# Wifi.net
KiCad netlist of a schematic drawn in Altium Designer
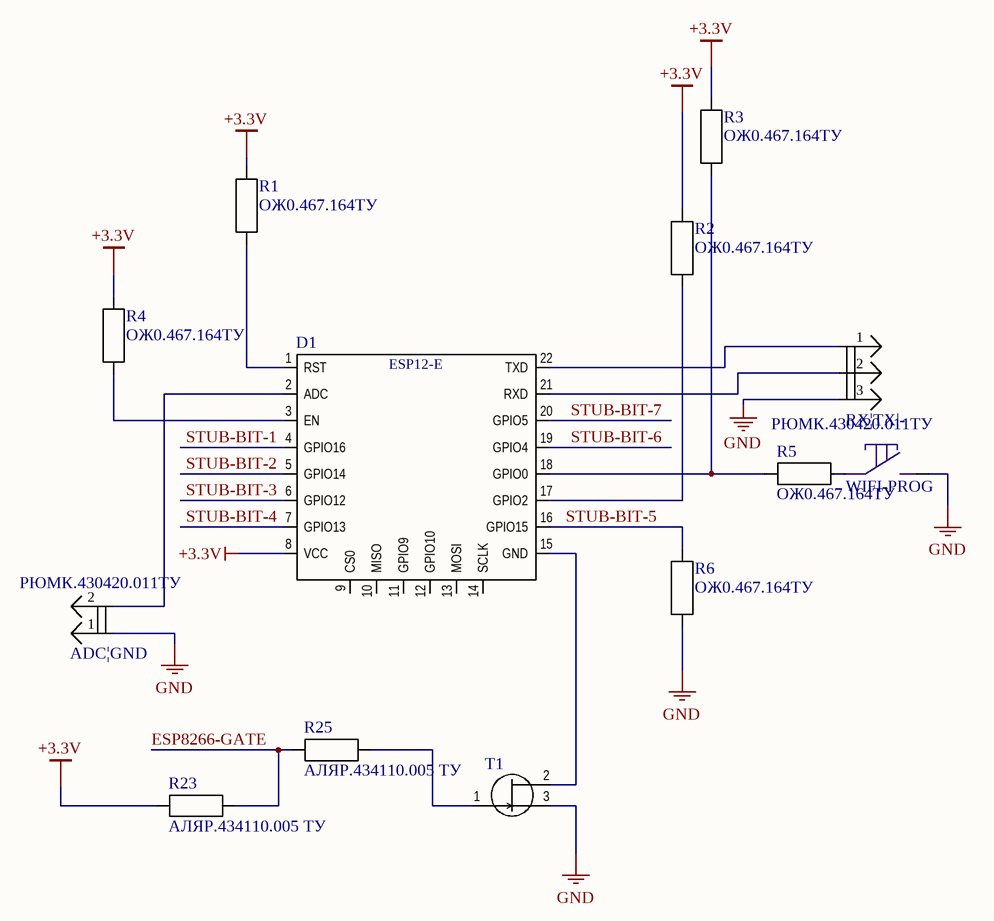
[diagram p0: Wifi модуль.SchDoc]

(export (version "E")
  (design (tool "Eeschema 10.0.6"))
  (components
    (comp (ref "ADC¦GND")
      (value "РЮМК.430420.011ТУ")
      (footprint "СНП346-2ВП21-1")
      (fields (field (name "MANUFACTURERPARTNUMBER") "Вилка СНП346-2ВП21-1"))
      (libsource (lib "РАЗЪЕМЫ") (part "СНП346-2ВП21-1"))
    )
    (comp (ref "D1")
      (value "~")
      (footprint "ESP12-E")
      (fields (field (name "MANUFACTURER") "ESPRESSIF") (field (name "MANUFACTURERPARTNUMBER") "ESP12E"))
      (libsource (lib "МИКРОСХЕМЫ") (part "ESP12-E"))
    )
    (comp (ref "R1")
      (value "ОЖ0.467.164ТУ")
      (footprint "Р1-8МП-0,125")
      (fields
        (field (name "TOLERANCE") "±1%-0,5-Л")
        (field (name "MANUFACTURERPARTNUMBER") "Р1-8МП-0,125-100 Ом±1%-0,5-Л")
      )
      (libsource (lib "РЕЗИСТОРЫ") (part "Р1-8МП-0,125-100 Ом±1%"))
    )
    (comp (ref "R2")
      (value "ОЖ0.467.164ТУ")
      (footprint "Р1-8МП-0,125")
      (fields
        (field (name "TOLERANCE") "±1%-0,5-Л")
        (field (name "MANUFACTURERPARTNUMBER") "Р1-8МП-0,125-100 Ом±1%-0,5-Л")
      )
      (libsource (lib "РЕЗИСТОРЫ") (part "Р1-8МП-0,125-100 Ом±1%"))
    )
    (comp (ref "R3")
      (value "ОЖ0.467.164ТУ")
      (footprint "Р1-8МП-0,125")
      (fields
        (field (name "TOLERANCE") "±1%-0,5-Л")
        (field (name "MANUFACTURERPARTNUMBER") "Р1-8МП-0,125-100 Ом±1%-0,5-Л")
      )
      (libsource (lib "РЕЗИСТОРЫ") (part "Р1-8МП-0,125-100 Ом±1%"))
    )
    (comp (ref "R4")
      (value "ОЖ0.467.164ТУ")
      (footprint "Р1-8МП-0,125")
      (fields
        (field (name "TOLERANCE") "±1%-0,5-Л")
        (field (name "MANUFACTURERPARTNUMBER") "Р1-8МП-0,125-100 Ом±1%-0,5-Л")
      )
      (libsource (lib "РЕЗИСТОРЫ") (part "Р1-8МП-0,125-100 Ом±1%"))
    )
    (comp (ref "R5")
      (value "ОЖ0.467.164ТУ")
      (footprint "Р1-8МП-0,125")
      (fields
        (field (name "TOLERANCE") "±1%-0,5-Л")
        (field (name "MANUFACTURERPARTNUMBER") "Р1-8МП-0,125-100 Ом±1%-0,5-Л")
      )
      (libsource (lib "РЕЗИСТОРЫ") (part "Р1-8МП-0,125-100 Ом±1%"))
    )
    (comp (ref "R6")
      (value "ОЖ0.467.164ТУ")
      (footprint "Р1-8МП-0,125")
      (fields
        (field (name "TOLERANCE") "±1%-0,5-Л")
        (field (name "MANUFACTURERPARTNUMBER") "Р1-8МП-0,125-100 Ом±1%-0,5-Л")
      )
      (libsource (lib "РЕЗИСТОРЫ") (part "Р1-8МП-0,125-100 Ом±1%"))
    )
    (comp (ref "R23")
      (value "АЛЯР.434110.005 ТУ")
      (footprint "Р1-12-0,125")
      (fields
        (field (name "TOLERANCE") "±1%-Л")
        (field (name "MANUFACTURERPARTNUMBER") "Р1-12-0,125-1,5 кОм±1%-Л")
      )
      (libsource (lib "РЕЗИСТОРЫ") (part "Р1-12-0,125-1,5 кОм±1%"))
    )
    (comp (ref "R25")
      (value "АЛЯР.434110.005 ТУ")
      (footprint "Р1-12-0,125")
      (fields
        (field (name "TOLERANCE") "±5%-Л")
        (field (name "MANUFACTURERPARTNUMBER") "Р1-12-0,125-200 Ом±5%-Л")
      )
      (libsource (lib "РЕЗИСТОРЫ") (part "Р1-12-0,125-200 Ом±5%"))
    )
    (comp (ref "RX¦TX¦-")
      (value "РЮМК.430420.011ТУ")
      (footprint "СНП346-3ВП21-1")
      (fields (field (name "MANUFACTURERPARTNUMBER") "Вилка СНП346-3ВП21-1"))
      (libsource (lib "РАЗЪЕМЫ") (part "СНП346-3ВП21-1"))
    )
    (comp (ref "T1")
      (value "~")
      (footprint "SOT23")
      (fields
        (field (name "MANUFACTURERPARTNUMBER") "IRLML2502")
        (field (name "MANUFACTURER") "International rectifier")
      )
      (libsource (lib "МИКРОСХЕМЫ") (part "IRLML2502"))
    )
    (comp (ref "WIFI-PROG")
      (value "Кнопка тактовая smd")
      (footprint "Кнопка тактовая smd")
      (libsource (lib "РАЗЪЕМЫ") (part "Кнопка тактовая smd"))
    )
  )
  (nets
    (net (code "1") (name "+3.3V") (class "Default")
      (node (ref "D1") (pin "8") (pinfunction "VCC_8") (pintype "passive"))
      (node (ref "R1") (pin "1") (pinfunction "1_1") (pintype "passive"))
      (node (ref "R2") (pin "2") (pinfunction "2_2") (pintype "passive"))
      (node (ref "R23") (pin "1") (pinfunction "1_1") (pintype "passive"))
      (node (ref "R3") (pin "2") (pinfunction "2_2") (pintype "passive"))
      (node (ref "R4") (pin "1") (pinfunction "1_1") (pintype "passive"))
    )
    (net (code "2") (name "/ESP8266-GATE") (class "Default")
      (node (ref "R23") (pin "2") (pinfunction "2_2") (pintype "passive"))
      (node (ref "R25") (pin "1") (pinfunction "1_1") (pintype "passive"))
    )
    (net (code "3") (name "/STUB-BIT-1") (class "Default")
      (node (ref "D1") (pin "4") (pinfunction "GPIO16_4") (pintype "passive"))
    )
    (net (code "4") (name "/STUB-BIT-2") (class "Default")
      (node (ref "D1") (pin "5") (pinfunction "GPIO14_5") (pintype "passive"))
    )
    (net (code "5") (name "/STUB-BIT-3") (class "Default")
      (node (ref "D1") (pin "6") (pinfunction "GPIO12_6") (pintype "passive"))
    )
    (net (code "6") (name "/STUB-BIT-4") (class "Default")
      (node (ref "D1") (pin "7") (pinfunction "GPIO13_7") (pintype "passive"))
    )
    (net (code "7") (name "/STUB-BIT-5") (class "Default")
      (node (ref "D1") (pin "16") (pinfunction "GPIO15_16") (pintype "passive"))
      (node (ref "R6") (pin "2") (pinfunction "2_2") (pintype "passive"))
    )
    (net (code "8") (name "/STUB-BIT-6") (class "Default")
      (node (ref "D1") (pin "19") (pinfunction "GPIO4_19") (pintype "passive"))
    )
    (net (code "9") (name "/STUB-BIT-7") (class "Default")
      (node (ref "D1") (pin "20") (pinfunction "GPIO5_20") (pintype "passive"))
    )
    (net (code "10") (name "1") (class "Default")
      (node (ref "WIFI-PROG") (pin "2") (pinfunction "2_2") (pintype "passive"))
    )
    (net (code "11") (name "3") (class "Default")
      (node (ref "WIFI-PROG") (pin "4") (pinfunction "4_4") (pintype "passive"))
    )
    (net (code "12") (name "GND") (class "Default")
      (node (ref "ADC¦GND") (pin "1") (pinfunction "1_1") (pintype "passive"))
      (node (ref "R6") (pin "1") (pinfunction "1_1") (pintype "passive"))
      (node (ref "RX¦TX¦-") (pin "3") (pinfunction "3_3") (pintype "passive"))
      (node (ref "T1") (pin "3") (pintype "passive"))
      (node (ref "WIFI-PROG") (pin "3") (pinfunction "3_3") (pintype "passive"))
    )
    (net (code "13") (name "Net-(D1-ADC)") (class "Default")
      (node (ref "ADC¦GND") (pin "2") (pinfunction "2_2") (pintype "passive"))
      (node (ref "D1") (pin "2") (pinfunction "ADC_2") (pintype "passive"))
    )
    (net (code "14") (name "Net-(D1-EN)") (class "Default")
      (node (ref "D1") (pin "3") (pinfunction "EN_3") (pintype "passive"))
      (node (ref "R4") (pin "2") (pinfunction "2_2") (pintype "passive"))
    )
    (net (code "15") (name "Net-(D1-GND)") (class "Default")
      (node (ref "D1") (pin "15") (pinfunction "GND_15") (pintype "passive"))
      (node (ref "T1") (pin "2") (pintype "passive"))
    )
    (net (code "16") (name "Net-(D1-GPIO0)") (class "Default")
      (node (ref "D1") (pin "18") (pinfunction "GPIO0_18") (pintype "passive"))
      (node (ref "R3") (pin "1") (pinfunction "1_1") (pintype "passive"))
      (node (ref "R5") (pin "1") (pinfunction "1_1") (pintype "passive"))
    )
    (net (code "17") (name "Net-(D1-GPIO2)") (class "Default")
      (node (ref "D1") (pin "17") (pinfunction "GPIO2_17") (pintype "passive"))
      (node (ref "R2") (pin "1") (pinfunction "1_1") (pintype "passive"))
    )
    (net (code "18") (name "Net-(D1-RST)") (class "Default")
      (node (ref "D1") (pin "1") (pinfunction "RST_1") (pintype "passive"))
      (node (ref "R1") (pin "2") (pinfunction "2_2") (pintype "passive"))
    )
    (net (code "19") (name "Net-(D1-RXD)") (class "Default")
      (node (ref "D1") (pin "21") (pinfunction "RXD_21") (pintype "passive"))
      (node (ref "RX¦TX¦-") (pin "2") (pinfunction "2_2") (pintype "passive"))
    )
    (net (code "20") (name "Net-(D1-TXD)") (class "Default")
      (node (ref "D1") (pin "22") (pinfunction "TXD_22") (pintype "passive"))
      (node (ref "RX¦TX¦-") (pin "1") (pinfunction "1_1") (pintype "passive"))
    )
    (net (code "21") (name "Net-(R5-Pad2)") (class "Default")
      (node (ref "R5") (pin "2") (pinfunction "2_2") (pintype "passive"))
      (node (ref "WIFI-PROG") (pin "1") (pinfunction "1_1") (pintype "passive"))
    )
    (net (code "22") (name "Net-(R25-Pad2)") (class "Default")
      (node (ref "R25") (pin "2") (pinfunction "2_2") (pintype "passive"))
      (node (ref "T1") (pin "1") (pintype "passive"))
    )
    (net (code "23") (name "unconnected-(D1-CS0-Pad9)") (class "Default")
      (node (ref "D1") (pin "9") (pinfunction "CS0_9") (pintype "passive"))
    )
    (net (code "24") (name "unconnected-(D1-GPIO9-Pad11)") (class "Default")
      (node (ref "D1") (pin "11") (pinfunction "GPIO9_11") (pintype "passive"))
    )
    (net (code "25") (name "unconnected-(D1-GPIO10-Pad12)") (class "Default")
      (node (ref "D1") (pin "12") (pinfunction "GPIO10_12") (pintype "passive"))
    )
    (net (code "26") (name "unconnected-(D1-MISO-Pad10)") (class "Default")
      (node (ref "D1") (pin "10") (pinfunction "MISO_10") (pintype "passive"))
    )
    (net (code "27") (name "unconnected-(D1-MOSI-Pad13)") (class "Default")
      (node (ref "D1") (pin "13") (pinfunction "MOSI_13") (pintype "passive"))
    )
    (net (code "28") (name "unconnected-(D1-SCLK-Pad14)") (class "Default")
      (node (ref "D1") (pin "14") (pinfunction "SCLK_14") (pintype "passive"))
    )
  )
)
